# Synthesizer_Build_part-24_ADSR_with_7555.net
KiCad netlist of a schematic drawn in Altium Designer
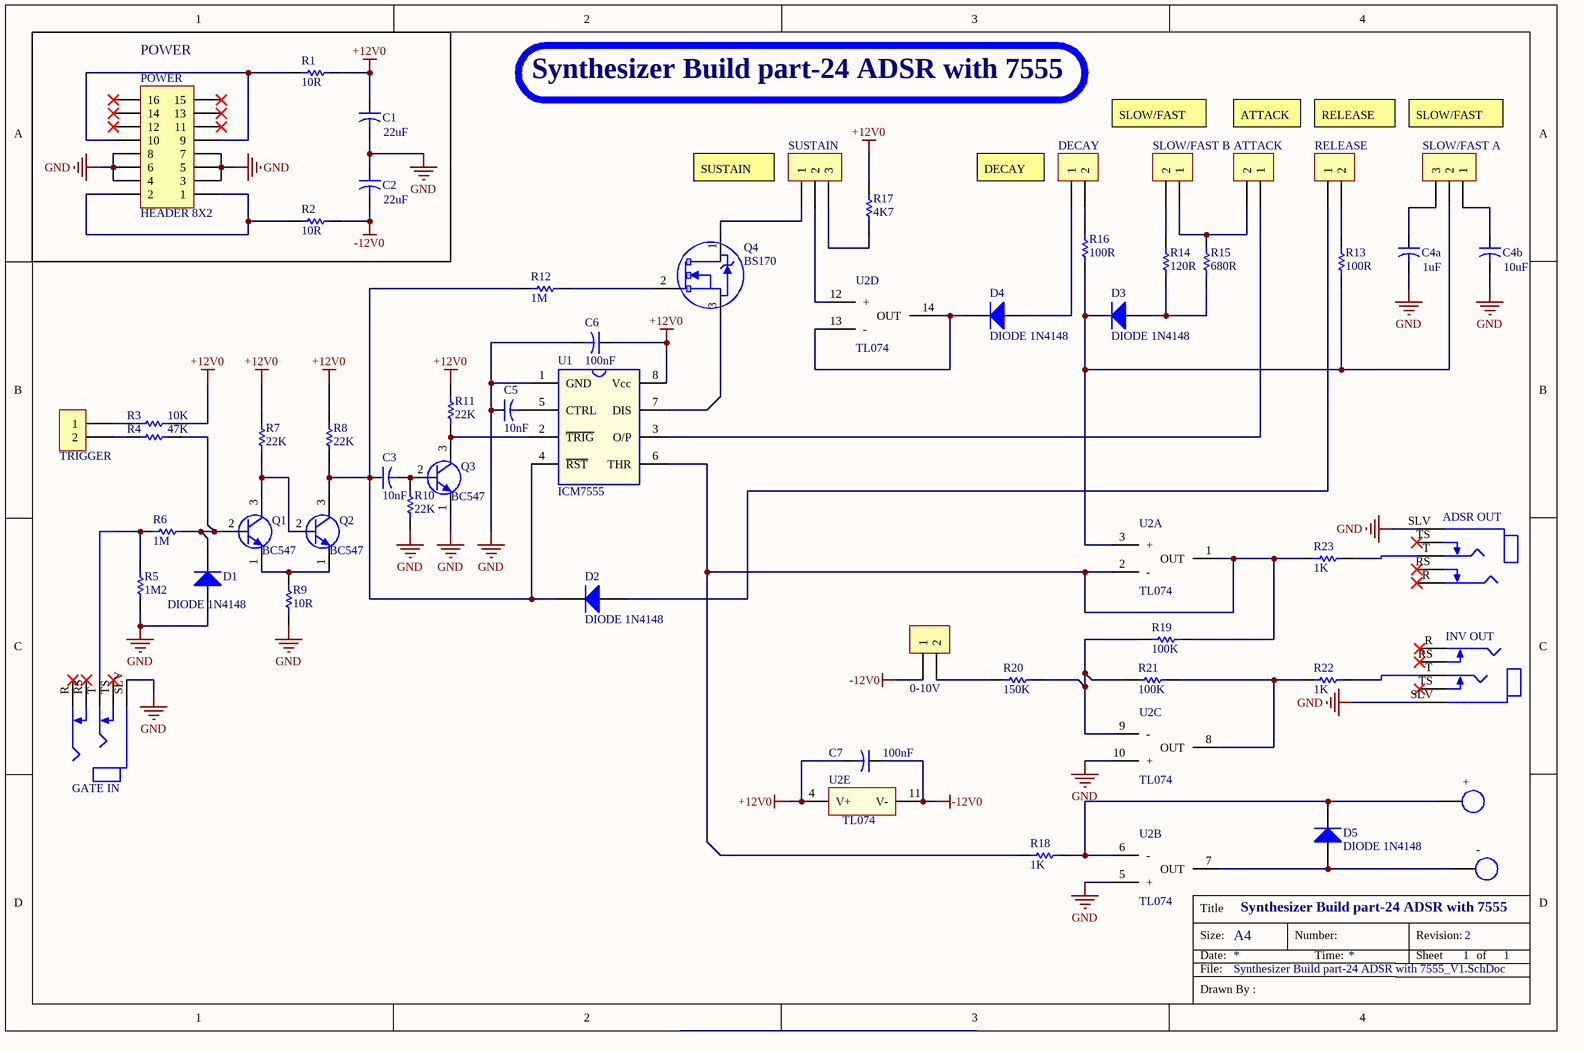
[diagram p0: Synthesizer Build part-24 ADSR with 7555_V1.SchDoc]

(export (version "E")
  (design (tool "Eeschema 10.0.6"))
  (components
    (comp (ref "+") (value "Hole") (footprint "LED_HOle") (libsource (lib "Schlib1") (part "Hole")))
    (comp (ref "-") (value "Hole") (footprint "LED_HOle") (libsource (lib "Schlib1") (part "Hole")))
    (comp (ref "0-10V")
      (value "SCREW TERMINAL 2WAY")
      (footprint "SCREW TERMINAL 2WAY")
      (description "SCREW TERMINAL 2WAY 5.08mm")
      (libsource (lib "Integrated_Library1") (part "SCREW TERMINAL 2WAY"))
    )
    (comp (ref "ADSR OUT")
      (value "N114BPCX")
      (footprint "Rev with streo jack:SWITCHCRAFT_N114BPCX")
      (description "Conn 1/4'' Phone Jack F 3 POS Solder ST Thru-Hole 5 Terminal 1 Port")
      (libsource (lib "112APCX") (part "N114BPCX"))
    )
    (comp (ref "ATTACK")
      (value "SCREW TERMINAL 2WAY")
      (footprint "SCREW TERMINAL 2WAY")
      (description "SCREW TERMINAL 2WAY 5.08mm")
      (libsource (lib "") (part "SCREW TERMINAL 2WAY_2"))
    )
    (comp (ref "C1")
      (value "22uF")
      (footprint "CAP 5X11")
      (libsource (lib "Integrated_Library1") (part "Capacitor Polar"))
    )
    (comp (ref "C2")
      (value "22uF")
      (footprint "CAP 5X11")
      (libsource (lib "Integrated_Library1") (part "Capacitor Polar"))
    )
    (comp (ref "C3")
      (value "10nF")
      (footprint "CAP RAD-0.3")
      (libsource (lib "Integrated_Library1") (part "Capacitor Polar"))
    )
    (comp (ref "C4a")
      (value "1uF")
      (footprint "CAP RAD-0.3")
      (libsource (lib "Integrated_Library1") (part "Capacitor Polar"))
    )
    (comp (ref "C4b")
      (value "10uF")
      (footprint "CAP 5X11")
      (libsource (lib "Integrated_Library1") (part "Capacitor Polar"))
    )
    (comp (ref "C5")
      (value "10nF")
      (footprint "CAP RAD-0.3")
      (libsource (lib "Integrated_Library1") (part "Capacitor Polar"))
    )
    (comp (ref "C6")
      (value "100nF")
      (footprint "CAP RAD-0.3")
      (libsource (lib "") (part "Capacitor Polar_1"))
    )
    (comp (ref "C7")
      (value "100nF")
      (footprint "CAP RAD-0.3")
      (libsource (lib "") (part "Capacitor Polar_1"))
    )
    (comp (ref "D1")
      (value "DIODE 1N4148")
      (footprint "DO-35")
      (description "Small Signal Fast Switching Diodes")
      (libsource (lib "Integrated_Library1") (part "DIODE 1N4148"))
    )
    (comp (ref "D2")
      (value "DIODE 1N4148")
      (footprint "DO-35")
      (description "Small Signal Fast Switching Diodes")
      (libsource (lib "Integrated_Library1") (part "DIODE 1N4148"))
    )
    (comp (ref "D3")
      (value "DIODE 1N4148")
      (footprint "DO-35")
      (description "Small Signal Fast Switching Diodes")
      (libsource (lib "Integrated_Library1") (part "DIODE 1N4148"))
    )
    (comp (ref "D4")
      (value "DIODE 1N4148")
      (footprint "DO-35")
      (description "Small Signal Fast Switching Diodes")
      (libsource (lib "Integrated_Library1") (part "DIODE 1N4148"))
    )
    (comp (ref "D5")
      (value "DIODE 1N4148")
      (footprint "DO-35")
      (description "Small Signal Fast Switching Diodes")
      (libsource (lib "Integrated_Library1") (part "DIODE 1N4148"))
    )
    (comp (ref "DECAY")
      (value "SCREW TERMINAL 2WAY")
      (footprint "SCREW TERMINAL 2WAY")
      (description "SCREW TERMINAL 2WAY 5.08mm")
      (libsource (lib "Integrated_Library1") (part "SCREW TERMINAL 2WAY"))
    )
    (comp (ref "GATE IN")
      (value "N114BPCX")
      (footprint "Rev with streo jack:SWITCHCRAFT_N114BPCX")
      (description "Conn 1/4'' Phone Jack F 3 POS Solder ST Thru-Hole 5 Terminal 1 Port")
      (libsource (lib "112APCX") (part "N114BPCX"))
    )
    (comp (ref "INV OUT")
      (value "N114BPCX")
      (footprint "Rev with streo jack:SWITCHCRAFT_N114BPCX")
      (description "Conn 1/4'' Phone Jack F 3 POS Solder ST Thru-Hole 5 Terminal 1 Port")
      (libsource (lib "112APCX") (part "N114BPCX"))
    )
    (comp (ref "POWER")
      (value "HEADER 8X2")
      (footprint "HEADER 8X2")
      (libsource (lib "Integrated_Library1") (part "HEADER 8X2"))
    )
    (comp (ref "Q1")
      (value "BC547")
      (footprint "TO92")
      (description "NPN Epitaxial Silicon Transistor")
      (libsource (lib "Integrated_Library1") (part "BC547"))
    )
    (comp (ref "Q2")
      (value "BC547")
      (footprint "TO92")
      (description "NPN Epitaxial Silicon Transistor")
      (libsource (lib "Integrated_Library1") (part "BC547"))
    )
    (comp (ref "Q3")
      (value "BC547")
      (footprint "TO92")
      (description "NPN Epitaxial Silicon Transistor")
      (libsource (lib "Integrated_Library1") (part "BC547"))
    )
    (comp (ref "Q4")
      (value "BS170")
      (footprint "TO92")
      (description "Small Signal N Channel MOSFET")
      (libsource (lib "Integrated_Library1") (part "BS170"))
    )
    (comp (ref "R1")
      (value "10R")
      (footprint "RES 6.2 x 0.5 x 2.3")
      (description "Resistor")
      (fields (field (name "PUBLISHER") "Altium Limited"))
      (libsource (lib "Schlib1") (part "Res2"))
    )
    (comp (ref "R2")
      (value "10R")
      (footprint "RES 6.2 x 0.5 x 2.3")
      (description "Resistor")
      (fields (field (name "PUBLISHER") "Altium Limited"))
      (libsource (lib "Schlib1") (part "Res2"))
    )
    (comp (ref "R3")
      (value "10K")
      (footprint "RES 6.2 x 0.5 x 2.3")
      (description "Resistor")
      (fields (field (name "PUBLISHER") "Altium Limited"))
      (libsource (lib "Schlib1") (part "Res2"))
    )
    (comp (ref "R4")
      (value "47K")
      (footprint "RES 6.2 x 0.5 x 2.3")
      (description "Resistor")
      (fields (field (name "PUBLISHER") "Altium Limited"))
      (libsource (lib "Schlib1") (part "Res2"))
    )
    (comp (ref "R5")
      (value "1M2")
      (footprint "RES 6.2 x 0.5 x 2.3")
      (description "Resistor")
      (fields (field (name "PUBLISHER") "Altium Limited"))
      (libsource (lib "Schlib1") (part "Res2"))
    )
    (comp (ref "R6")
      (value "1M")
      (footprint "RES 6.2 x 0.5 x 2.3")
      (description "Resistor")
      (fields (field (name "PUBLISHER") "Altium Limited"))
      (libsource (lib "Schlib1") (part "Res2"))
    )
    (comp (ref "R7")
      (value "22K")
      (footprint "RES 6.2 x 0.5 x 2.3")
      (description "Resistor")
      (fields (field (name "PUBLISHER") "Altium Limited"))
      (libsource (lib "Schlib1") (part "Res2"))
    )
    (comp (ref "R8")
      (value "22K")
      (footprint "RES 6.2 x 0.5 x 2.3")
      (description "Resistor")
      (fields (field (name "PUBLISHER") "Altium Limited"))
      (libsource (lib "Schlib1") (part "Res2"))
    )
    (comp (ref "R9")
      (value "10R")
      (footprint "RES 6.2 x 0.5 x 2.3")
      (description "Resistor")
      (fields (field (name "PUBLISHER") "Altium Limited"))
      (libsource (lib "Schlib1") (part "Res2"))
    )
    (comp (ref "R10")
      (value "22K")
      (footprint "RES 6.2 x 0.5 x 2.3")
      (description "Resistor")
      (fields (field (name "PUBLISHER") "Altium Limited"))
      (libsource (lib "Schlib1") (part "Res2"))
    )
    (comp (ref "R11")
      (value "22K")
      (footprint "RES 6.2 x 0.5 x 2.3")
      (description "Resistor")
      (fields (field (name "PUBLISHER") "Altium Limited"))
      (libsource (lib "Schlib1") (part "Res2"))
    )
    (comp (ref "R12")
      (value "1M")
      (footprint "RES 6.2 x 0.5 x 2.3")
      (description "Resistor")
      (fields (field (name "PUBLISHER") "Altium Limited"))
      (libsource (lib "Schlib1") (part "Res2"))
    )
    (comp (ref "R13")
      (value "100R")
      (footprint "RES 6.2 x 0.5 x 2.3")
      (description "Resistor")
      (fields (field (name "PUBLISHER") "Altium Limited"))
      (libsource (lib "Schlib1") (part "Res2"))
    )
    (comp (ref "R14")
      (value "120R")
      (footprint "RES 6.2 x 0.5 x 2.3")
      (description "Resistor")
      (fields (field (name "PUBLISHER") "Altium Limited"))
      (libsource (lib "Schlib1") (part "Res2"))
    )
    (comp (ref "R15")
      (value "680R")
      (footprint "RES 6.2 x 0.5 x 2.3")
      (description "Resistor")
      (fields (field (name "PUBLISHER") "Altium Limited"))
      (libsource (lib "Schlib1") (part "Res2"))
    )
    (comp (ref "R16")
      (value "100R")
      (footprint "RES 6.2 x 0.5 x 2.3")
      (description "Resistor")
      (fields (field (name "PUBLISHER") "Altium Limited"))
      (libsource (lib "Schlib1") (part "Res2"))
    )
    (comp (ref "R17")
      (value "4K7")
      (footprint "RES 6.2 x 0.5 x 2.3")
      (description "Resistor")
      (fields (field (name "PUBLISHER") "Altium Limited"))
      (libsource (lib "Schlib1") (part "Res2"))
    )
    (comp (ref "R18")
      (value "1K")
      (footprint "RES 6.2 x 0.5 x 2.3")
      (description "Resistor")
      (fields (field (name "PUBLISHER") "Altium Limited"))
      (libsource (lib "Schlib1") (part "Res2"))
    )
    (comp (ref "R19")
      (value "100K")
      (footprint "RES 6.2 x 0.5 x 2.3")
      (description "Resistor")
      (fields (field (name "PUBLISHER") "Altium Limited"))
      (libsource (lib "Schlib1") (part "Res2"))
    )
    (comp (ref "R20")
      (value "150K")
      (footprint "RES 6.2 x 0.5 x 2.3")
      (description "Resistor")
      (fields (field (name "PUBLISHER") "Altium Limited"))
      (libsource (lib "Schlib1") (part "Res2"))
    )
    (comp (ref "R21")
      (value "100K")
      (footprint "RES 6.2 x 0.5 x 2.3")
      (description "Resistor")
      (fields (field (name "PUBLISHER") "Altium Limited"))
      (libsource (lib "Schlib1") (part "Res2"))
    )
    (comp (ref "R22")
      (value "1K")
      (footprint "RES 6.2 x 0.5 x 2.3")
      (description "Resistor")
      (fields (field (name "PUBLISHER") "Altium Limited"))
      (libsource (lib "Schlib1") (part "Res2"))
    )
    (comp (ref "R23")
      (value "1K")
      (footprint "RES 6.2 x 0.5 x 2.3")
      (description "Resistor")
      (fields (field (name "PUBLISHER") "Altium Limited"))
      (libsource (lib "Schlib1") (part "Res2"))
    )
    (comp (ref "RELEASE")
      (value "SCREW TERMINAL 2WAY")
      (footprint "SCREW TERMINAL 2WAY")
      (description "SCREW TERMINAL 2WAY 5.08mm")
      (libsource (lib "Integrated_Library1") (part "SCREW TERMINAL 2WAY"))
    )
    (comp (ref "SLOW/FAST A")
      (value "SCREW TERMINAL 3WAY")
      (footprint "SCREW TERMINAL 3WAY")
      (description "SCREW TERMINAL 3WAY 5.08mm")
      (libsource (lib "Integrated_Library1") (part "SCREW TERMINAL 3WAY"))
    )
    (comp (ref "SLOW/FAST B")
      (value "SCREW TERMINAL 2WAY")
      (footprint "SCREW TERMINAL 2WAY")
      (description "SCREW TERMINAL 2WAY 5.08mm")
      (libsource (lib "") (part "SCREW TERMINAL 2WAY_2"))
    )
    (comp (ref "SUSTAIN")
      (value "SCREW TERMINAL 3WAY")
      (footprint "SCREW TERMINAL 3WAY")
      (description "SCREW TERMINAL 3WAY 5.08mm")
      (libsource (lib "") (part "SCREW TERMINAL 3WAY_1"))
    )
    (comp (ref "TRIGGER")
      (value "SCREW TERMINAL 2WAY")
      (footprint "SCREW TERMINAL 2WAY")
      (description "SCREW TERMINAL 2WAY 5.08mm")
      (libsource (lib "") (part "SCREW TERMINAL 2WAY_1"))
    )
    (comp (ref "U1")
      (value "ICM7555")
      (footprint "DIP 8 PIN")
      (description "General purpose CMOS timer")
      (libsource (lib "Schlib1") (part "ICM7555"))
    )
    (comp (ref "U2")
      (value "TL074")
      (footprint "DIP 14 PIN")
      (description "Low-Noise FET-Input Operational Amplifiers")
      (libsource (lib "") (part "TL074_1"))
    )
  )
  (nets
    (net (code "1") (name "+12V0") (class "Default")
      (node (ref "C1") (pin "1") (pinfunction "1_1") (pintype "passive"))
      (node (ref "C6") (pin "1") (pinfunction "1_1") (pintype "passive"))
      (node (ref "C7") (pin "2") (pinfunction "2_2") (pintype "passive"))
      (node (ref "R1") (pin "1") (pinfunction "1_1") (pintype "passive"))
      (node (ref "R11") (pin "2") (pinfunction "2_2") (pintype "passive"))
      (node (ref "R17") (pin "1") (pinfunction "1_1") (pintype "passive"))
      (node (ref "R3") (pin "2") (pinfunction "2_2") (pintype "passive"))
      (node (ref "R7") (pin "2") (pinfunction "2_2") (pintype "passive"))
      (node (ref "R8") (pin "2") (pinfunction "2_2") (pintype "passive"))
      (node (ref "U1") (pin "8") (pinfunction "Vcc_8") (pintype "passive"))
      (node (ref "U2") (pin "4") (pinfunction "V+_4") (pintype "passive"))
    )
    (net (code "2") (name "-12V0") (class "Default")
      (node (ref "0-10V") (pin "1") (pinfunction "1_1") (pintype "passive"))
      (node (ref "C2") (pin "2") (pinfunction "2_2") (pintype "passive"))
      (node (ref "C7") (pin "1") (pinfunction "1_1") (pintype "passive"))
      (node (ref "R2") (pin "1") (pinfunction "1_1") (pintype "passive"))
      (node (ref "U2") (pin "11") (pinfunction "V-_11") (pintype "passive"))
    )
    (net (code "3") (name "GND") (class "Default")
      (node (ref "ADSR OUT") (pin "SLV") (pinfunction "SLEEVE_SLV") (pintype "passive"))
      (node (ref "C1") (pin "2") (pinfunction "2_2") (pintype "passive"))
      (node (ref "C2") (pin "1") (pinfunction "1_1") (pintype "passive"))
      (node (ref "C4a") (pin "2") (pinfunction "2_2") (pintype "passive"))
      (node (ref "C4b") (pin "2") (pinfunction "2_2") (pintype "passive"))
      (node (ref "C5") (pin "1") (pinfunction "1_1") (pintype "passive"))
      (node (ref "C6") (pin "2") (pinfunction "2_2") (pintype "passive"))
      (node (ref "D1") (pin "1") (pinfunction "A_1") (pintype "passive"))
      (node (ref "GATE IN") (pin "SLV") (pinfunction "SLEEVE_SLV") (pintype "passive"))
      (node (ref "INV OUT") (pin "SLV") (pinfunction "SLEEVE_SLV") (pintype "passive"))
      (node (ref "POWER") (pin "3") (pinfunction "3_3") (pintype "passive"))
      (node (ref "POWER") (pin "4") (pinfunction "4_4") (pintype "passive"))
      (node (ref "POWER") (pin "5") (pinfunction "5_5") (pintype "passive"))
      (node (ref "POWER") (pin "6") (pinfunction "6_6") (pintype "passive"))
      (node (ref "POWER") (pin "7") (pinfunction "7_7") (pintype "passive"))
      (node (ref "POWER") (pin "8") (pinfunction "8_8") (pintype "passive"))
      (node (ref "Q3") (pin "1") (pinfunction "C_1") (pintype "passive"))
      (node (ref "R10") (pin "1") (pinfunction "1_1") (pintype "passive"))
      (node (ref "R5") (pin "1") (pinfunction "1_1") (pintype "passive"))
      (node (ref "R9") (pin "1") (pinfunction "1_1") (pintype "passive"))
      (node (ref "U1") (pin "1") (pinfunction "GND_1") (pintype "passive"))
      (node (ref "U2") (pin "10") (pinfunction "+_10") (pintype "passive"))
      (node (ref "U2") (pin "5") (pinfunction "+_5") (pintype "passive"))
    )
    (net (code "4") (name "Net-(0-10V-Pad2)") (class "Default")
      (node (ref "0-10V") (pin "2") (pinfunction "2_2") (pintype "passive"))
      (node (ref "R20") (pin "2") (pinfunction "2_2") (pintype "passive"))
    )
    (net (code "5") (name "Net-(ADSR OUT-TIP)") (class "Default")
      (node (ref "ADSR OUT") (pin "T") (pinfunction "TIP_T") (pintype "passive"))
      (node (ref "R23") (pin "1") (pinfunction "1_1") (pintype "passive"))
    )
    (net (code "6") (name "Net-(ATTACK-Pad2)") (class "Default")
      (node (ref "ATTACK") (pin "2") (pinfunction "2_2") (pintype "passive"))
      (node (ref "R15") (pin "1") (pinfunction "1_1") (pintype "passive"))
      (node (ref "SLOW/FAST B") (pin "1") (pinfunction "1_1") (pintype "passive"))
    )
    (net (code "7") (name "Net-(C4a-Pad1)") (class "Default")
      (node (ref "C4a") (pin "1") (pinfunction "1_1") (pintype "passive"))
      (node (ref "SLOW/FAST A") (pin "3") (pinfunction "3_3") (pintype "passive"))
    )
    (net (code "8") (name "Net-(C4b-Pad1)") (class "Default")
      (node (ref "C4b") (pin "1") (pinfunction "1_1") (pintype "passive"))
      (node (ref "SLOW/FAST A") (pin "1") (pinfunction "1_1") (pintype "passive"))
    )
    (net (code "9") (name "Net-(D1-K)") (class "Default")
      (node (ref "D1") (pin "2") (pinfunction "K_2") (pintype "passive"))
      (node (ref "Q1") (pin "2") (pinfunction "B_2") (pintype "passive"))
      (node (ref "R4") (pin "2") (pinfunction "2_2") (pintype "passive"))
      (node (ref "R6") (pin "1") (pinfunction "1_1") (pintype "passive"))
    )
    (net (code "10") (name "Net-(D2-A)") (class "Default")
      (node (ref "D2") (pin "1") (pinfunction "A_1") (pintype "passive"))
      (node (ref "RELEASE") (pin "1") (pinfunction "1_1") (pintype "passive"))
    )
    (net (code "11") (name "Net-(D2-K)") (class "Default")
      (node (ref "C3") (pin "1") (pinfunction "1_1") (pintype "passive"))
      (node (ref "D2") (pin "2") (pinfunction "K_2") (pintype "passive"))
      (node (ref "Q2") (pin "3") (pinfunction "E_3") (pintype "passive"))
      (node (ref "R12") (pin "2") (pinfunction "2_2") (pintype "passive"))
      (node (ref "R8") (pin "1") (pinfunction "1_1") (pintype "passive"))
      (node (ref "U1") (pin "4") (pinfunction "~{RST}_4") (pintype "passive"))
    )
    (net (code "12") (name "Net-(D3-A)") (class "Default")
      (node (ref "D3") (pin "1") (pinfunction "A_1") (pintype "passive"))
      (node (ref "R14") (pin "1") (pinfunction "1_1") (pintype "passive"))
      (node (ref "R15") (pin "2") (pinfunction "2_2") (pintype "passive"))
    )
    (net (code "13") (name "Net-(D3-K)") (class "Default")
      (node (ref "D3") (pin "2") (pinfunction "K_2") (pintype "passive"))
      (node (ref "R13") (pin "2") (pinfunction "2_2") (pintype "passive"))
      (node (ref "R16") (pin "2") (pinfunction "2_2") (pintype "passive"))
      (node (ref "SLOW/FAST A") (pin "2") (pinfunction "2_2") (pintype "passive"))
      (node (ref "U2") (pin "3") (pinfunction "+_3") (pintype "passive"))
    )
    (net (code "14") (name "Net-(D4-A)") (class "Default")
      (node (ref "D4") (pin "1") (pinfunction "A_1") (pintype "passive"))
      (node (ref "DECAY") (pin "1") (pinfunction "1_1") (pintype "passive"))
    )
    (net (code "15") (name "Net-(D4-K)") (class "Default")
      (node (ref "D4") (pin "2") (pinfunction "K_2") (pintype "passive"))
      (node (ref "U2") (pin "13") (pinfunction "-_13") (pintype "passive"))
      (node (ref "U2") (pin "14") (pinfunction "OUT_14") (pintype "passive"))
    )
    (net (code "16") (name "Net-(D5-A)") (class "Default")
      (node (ref "-") (pin "1") (pinfunction "1_1") (pintype "passive"))
      (node (ref "D5") (pin "1") (pinfunction "A_1") (pintype "passive"))
      (node (ref "U2") (pin "7") (pinfunction "OUT_7") (pintype "passive"))
    )
    (net (code "17") (name "Net-(D5-K)") (class "Default")
      (node (ref "+") (pin "1") (pinfunction "1_1") (pintype "passive"))
      (node (ref "D5") (pin "2") (pinfunction "K_2") (pintype "passive"))
      (node (ref "R18") (pin "1") (pinfunction "1_1") (pintype "passive"))
      (node (ref "U2") (pin "6") (pinfunction "-_6") (pintype "passive"))
    )
    (net (code "18") (name "Net-(DECAY-Pad2)") (class "Default")
      (node (ref "DECAY") (pin "2") (pinfunction "2_2") (pintype "passive"))
      (node (ref "R16") (pin "1") (pinfunction "1_1") (pintype "passive"))
    )
    (net (code "19") (name "Net-(GATE IN-TIP)") (class "Default")
      (node (ref "GATE IN") (pin "T") (pinfunction "TIP_T") (pintype "passive"))
      (node (ref "R5") (pin "2") (pinfunction "2_2") (pintype "passive"))
      (node (ref "R6") (pin "2") (pinfunction "2_2") (pintype "passive"))
    )
    (net (code "20") (name "Net-(INV OUT-TIP)") (class "Default")
      (node (ref "INV OUT") (pin "T") (pinfunction "TIP_T") (pintype "passive"))
      (node (ref "R22") (pin "1") (pinfunction "1_1") (pintype "passive"))
    )
    (net (code "21") (name "Net-(POWER-Pad1)") (class "Default")
      (node (ref "POWER") (pin "1") (pinfunction "1_1") (pintype "passive"))
      (node (ref "POWER") (pin "2") (pinfunction "2_2") (pintype "passive"))
      (node (ref "R2") (pin "2") (pinfunction "2_2") (pintype "passive"))
    )
    (net (code "22") (name "Net-(POWER-Pad10)") (class "Default")
      (node (ref "POWER") (pin "10") (pinfunction "10_10") (pintype "passive"))
      (node (ref "POWER") (pin "9") (pinfunction "9_9") (pintype "passive"))
      (node (ref "R1") (pin "2") (pinfunction "2_2") (pintype "passive"))
    )
    (net (code "23") (name "Net-(Q1-C)") (class "Default")
      (node (ref "Q1") (pin "1") (pinfunction "C_1") (pintype "passive"))
      (node (ref "Q2") (pin "1") (pinfunction "C_1") (pintype "passive"))
      (node (ref "R9") (pin "2") (pinfunction "2_2") (pintype "passive"))
    )
    (net (code "24") (name "Net-(Q1-E)") (class "Default")
      (node (ref "Q1") (pin "3") (pinfunction "E_3") (pintype "passive"))
      (node (ref "Q2") (pin "2") (pinfunction "B_2") (pintype "passive"))
      (node (ref "R7") (pin "1") (pinfunction "1_1") (pintype "passive"))
    )
    (net (code "25") (name "Net-(Q3-B)") (class "Default")
      (node (ref "C3") (pin "2") (pinfunction "2_2") (pintype "passive"))
      (node (ref "Q3") (pin "2") (pinfunction "B_2") (pintype "passive"))
      (node (ref "R10") (pin "2") (pinfunction "2_2") (pintype "passive"))
    )
    (net (code "26") (name "Net-(Q3-E)") (class "Default")
      (node (ref "Q3") (pin "3") (pinfunction "E_3") (pintype "passive"))
      (node (ref "R11") (pin "1") (pinfunction "1_1") (pintype "passive"))
      (node (ref "U1") (pin "2") (pinfunction "~{TRIG}_2") (pintype "passive"))
    )
    (net (code "27") (name "Net-(Q4-D)") (class "Default")
      (node (ref "Q4") (pin "1") (pinfunction "D_1") (pintype "passive"))
      (node (ref "SUSTAIN") (pin "1") (pinfunction "1_1") (pintype "passive"))
    )
    (net (code "28") (name "Net-(Q4-G)") (class "Default")
      (node (ref "Q4") (pin "2") (pinfunction "G_2") (pintype "passive"))
      (node (ref "R12") (pin "1") (pinfunction "1_1") (pintype "passive"))
    )
    (net (code "29") (name "Net-(Q4-S)") (class "Default")
      (node (ref "Q4") (pin "3") (pinfunction "S_3") (pintype "passive"))
      (node (ref "U1") (pin "7") (pinfunction "DIS_7") (pintype "passive"))
    )
    (net (code "30") (name "Net-(R3-Pad1)") (class "Default")
      (node (ref "R3") (pin "1") (pinfunction "1_1") (pintype "passive"))
      (node (ref "TRIGGER") (pin "1") (pinfunction "1_1") (pintype "passive"))
    )
    (net (code "31") (name "Net-(R4-Pad1)") (class "Default")
      (node (ref "R4") (pin "1") (pinfunction "1_1") (pintype "passive"))
      (node (ref "TRIGGER") (pin "2") (pinfunction "2_2") (pintype "passive"))
    )
    (net (code "32") (name "Net-(R13-Pad1)") (class "Default")
      (node (ref "R13") (pin "1") (pinfunction "1_1") (pintype "passive"))
      (node (ref "RELEASE") (pin "2") (pinfunction "2_2") (pintype "passive"))
    )
    (net (code "33") (name "Net-(R14-Pad2)") (class "Default")
      (node (ref "R14") (pin "2") (pinfunction "2_2") (pintype "passive"))
      (node (ref "SLOW/FAST B") (pin "2") (pinfunction "2_2") (pintype "passive"))
    )
    (net (code "34") (name "Net-(R17-Pad2)") (class "Default")
      (node (ref "R17") (pin "2") (pinfunction "2_2") (pintype "passive"))
      (node (ref "SUSTAIN") (pin "3") (pinfunction "3_3") (pintype "passive"))
    )
    (net (code "35") (name "Net-(U1-CTRL)") (class "Default")
      (node (ref "C5") (pin "2") (pinfunction "2_2") (pintype "passive"))
      (node (ref "U1") (pin "5") (pinfunction "CTRL_5") (pintype "passive"))
    )
    (net (code "36") (name "Net-(U1-O{slash}P)") (class "Default")
      (node (ref "ATTACK") (pin "1") (pinfunction "1_1") (pintype "passive"))
      (node (ref "U1") (pin "3") (pinfunction "O/P_3") (pintype "passive"))
    )
    (net (code "37") (name "Net-(U1-THR)") (class "Default")
      (node (ref "R18") (pin "2") (pinfunction "2_2") (pintype "passive"))
      (node (ref "R19") (pin "1") (pinfunction "1_1") (pintype "passive"))
      (node (ref "R23") (pin "2") (pinfunction "2_2") (pintype "passive"))
      (node (ref "U1") (pin "6") (pinfunction "THR_6") (pintype "passive"))
      (node (ref "U2") (pin "1") (pinfunction "OUT_1") (pintype "passive"))
      (node (ref "U2") (pin "2") (pinfunction "-_2") (pintype "passive"))
    )
    (net (code "38") (name "Net-(U2C--)") (class "Default")
      (node (ref "R19") (pin "2") (pinfunction "2_2") (pintype "passive"))
      (node (ref "R20") (pin "1") (pinfunction "1_1") (pintype "passive"))
      (node (ref "R21") (pin "2") (pinfunction "2_2") (pintype "passive"))
      (node (ref "U2") (pin "9") (pinfunction "-_9") (pintype "passive"))
    )
    (net (code "39") (name "Net-(U2C-OUT)") (class "Default")
      (node (ref "R21") (pin "1") (pinfunction "1_1") (pintype "passive"))
      (node (ref "R22") (pin "2") (pinfunction "2_2") (pintype "passive"))
      (node (ref "U2") (pin "8") (pinfunction "OUT_8") (pintype "passive"))
    )
    (net (code "40") (name "Net-(U2D-+)") (class "Default")
      (node (ref "SUSTAIN") (pin "2") (pinfunction "2_2") (pintype "passive"))
      (node (ref "U2") (pin "12") (pinfunction "+_12") (pintype "passive"))
    )
    (net (code "41") (name "unconnected-(ADSR OUT-RING-PadR)") (class "Default")
      (node (ref "ADSR OUT") (pin "R") (pinfunction "RING_R") (pintype "passive+no_connect"))
    )
    (net (code "42") (name "unconnected-(ADSR OUT-RING_SHUNT-PadRS)") (class "Default")
      (node (ref "ADSR OUT") (pin "RS") (pinfunction "RING_SHUNT_RS") (pintype "passive+no_connect"))
    )
    (net (code "43") (name "unconnected-(ADSR OUT-TIP_SHUNT-PadTS)") (class "Default")
      (node (ref "ADSR OUT") (pin "TS") (pinfunction "TIP_SHUNT_TS") (pintype "passive+no_connect"))
    )
    (net (code "44") (name "unconnected-(GATE IN-RING-PadR)") (class "Default")
      (node (ref "GATE IN") (pin "R") (pinfunction "RING_R") (pintype "passive+no_connect"))
    )
    (net (code "45") (name "unconnected-(GATE IN-RING_SHUNT-PadRS)") (class "Default")
      (node (ref "GATE IN") (pin "RS") (pinfunction "RING_SHUNT_RS") (pintype "passive+no_connect"))
    )
    (net (code "46") (name "unconnected-(GATE IN-TIP_SHUNT-PadTS)") (class "Default")
      (node (ref "GATE IN") (pin "TS") (pinfunction "TIP_SHUNT_TS") (pintype "passive+no_connect"))
    )
    (net (code "47") (name "unconnected-(INV OUT-RING-PadR)") (class "Default")
      (node (ref "INV OUT") (pin "R") (pinfunction "RING_R") (pintype "passive+no_connect"))
    )
    (net (code "48") (name "unconnected-(INV OUT-RING_SHUNT-PadRS)") (class "Default")
      (node (ref "INV OUT") (pin "RS") (pinfunction "RING_SHUNT_RS") (pintype "passive+no_connect"))
    )
    (net (code "49") (name "unconnected-(INV OUT-TIP_SHUNT-PadTS)") (class "Default")
      (node (ref "INV OUT") (pin "TS") (pinfunction "TIP_SHUNT_TS") (pintype "passive+no_connect"))
    )
    (net (code "50") (name "unconnected-(POWER-Pad11)") (class "Default")
      (node (ref "POWER") (pin "11") (pinfunction "11_11") (pintype "passive+no_connect"))
    )
    (net (code "51") (name "unconnected-(POWER-Pad12)") (class "Default")
      (node (ref "POWER") (pin "12") (pinfunction "12_12") (pintype "passive+no_connect"))
    )
    (net (code "52") (name "unconnected-(POWER-Pad13)") (class "Default")
      (node (ref "POWER") (pin "13") (pinfunction "13_13") (pintype "passive+no_connect"))
    )
    (net (code "53") (name "unconnected-(POWER-Pad14)") (class "Default")
      (node (ref "POWER") (pin "14") (pinfunction "14_14") (pintype "passive+no_connect"))
    )
    (net (code "54") (name "unconnected-(POWER-Pad15)") (class "Default")
      (node (ref "POWER") (pin "15") (pinfunction "15_15") (pintype "passive+no_connect"))
    )
    (net (code "55") (name "unconnected-(POWER-Pad16)") (class "Default")
      (node (ref "POWER") (pin "16") (pinfunction "16_16") (pintype "passive+no_connect"))
    )
  )
)
